# NyanTimer-v7.net
KiCad netlist of a schematic drawn in EAGLE
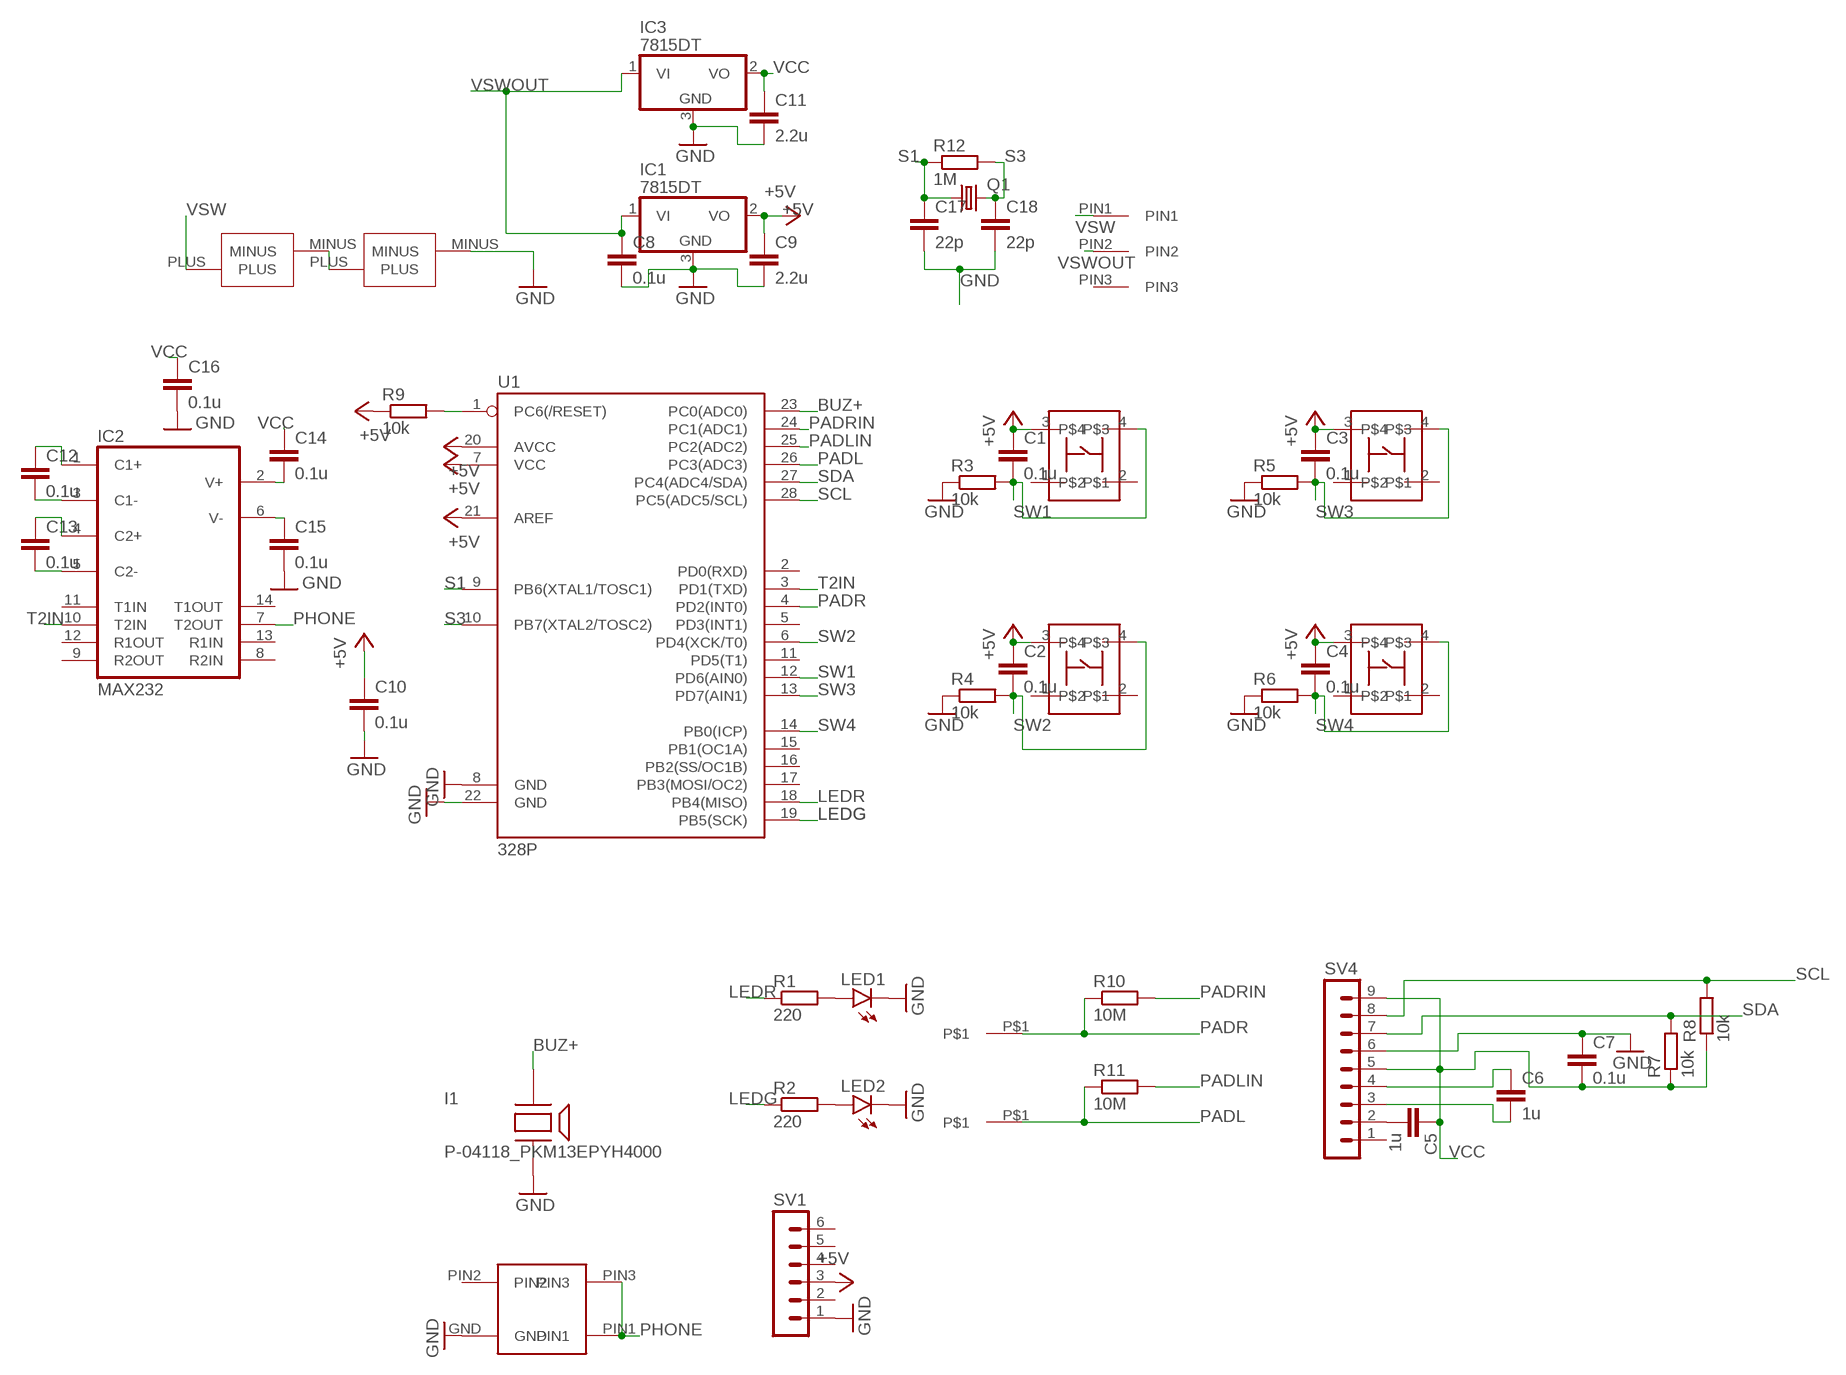
[diagram p0: schematic, sheet 1]

(export (version "E")
  (design (tool "Eeschema 10.0.6"))
  (components
    (comp (ref "BT1")
      (value "AKIZUKI_CR2032")
      (footprint "eagle-import:AKIZUKI_CR2032")
      (libsource (lib "eagle-import") (part "AKIZUKI_CR2032"))
    )
    (comp (ref "BT2")
      (value "AKIZUKI_CR2032")
      (footprint "eagle-import:AKIZUKI_CR2032")
      (libsource (lib "eagle-import") (part "AKIZUKI_CR2032"))
    )
    (comp (ref "C1")
      (value "0.1u")
      (footprint "eagle-import:C025-024X044")
      (libsource (lib "eagle-import") (part "C-EU025-024X044"))
    )
    (comp (ref "C2")
      (value "0.1u")
      (footprint "eagle-import:C025-024X044")
      (libsource (lib "eagle-import") (part "C-EU025-024X044"))
    )
    (comp (ref "C3")
      (value "0.1u")
      (footprint "eagle-import:C025-024X044")
      (libsource (lib "eagle-import") (part "C-EU025-024X044"))
    )
    (comp (ref "C4")
      (value "0.1u")
      (footprint "eagle-import:C025-024X044")
      (libsource (lib "eagle-import") (part "C-EU025-024X044"))
    )
    (comp (ref "C5")
      (value "1u")
      (footprint "eagle-import:C025-024X044")
      (libsource (lib "eagle-import") (part "C-EU025-024X044"))
    )
    (comp (ref "C6")
      (value "1u")
      (footprint "eagle-import:C025-024X044")
      (libsource (lib "eagle-import") (part "C-EU025-024X044"))
    )
    (comp (ref "C7")
      (value "0.1u")
      (footprint "eagle-import:C025-024X044")
      (libsource (lib "eagle-import") (part "C-EU025-024X044"))
    )
    (comp (ref "C8")
      (value "0.1u")
      (footprint "eagle-import:C025-024X044")
      (libsource (lib "eagle-import") (part "C-EU025-024X044"))
    )
    (comp (ref "C9")
      (value "2.2u")
      (footprint "eagle-import:C025-024X044")
      (libsource (lib "eagle-import") (part "C-EU025-024X044"))
    )
    (comp (ref "C10")
      (value "0.1u")
      (footprint "eagle-import:C025-024X044")
      (libsource (lib "eagle-import") (part "C-EU025-024X044"))
    )
    (comp (ref "C11")
      (value "2.2u")
      (footprint "eagle-import:C025-024X044")
      (libsource (lib "eagle-import") (part "C-EU025-024X044"))
    )
    (comp (ref "C12")
      (value "0.1u")
      (footprint "eagle-import:C025-024X044")
      (libsource (lib "eagle-import") (part "C-EU025-024X044"))
    )
    (comp (ref "C13")
      (value "0.1u")
      (footprint "eagle-import:C025-024X044")
      (libsource (lib "eagle-import") (part "C-EU025-024X044"))
    )
    (comp (ref "C14")
      (value "0.1u")
      (footprint "eagle-import:C025-024X044")
      (libsource (lib "eagle-import") (part "C-EU025-024X044"))
    )
    (comp (ref "C15")
      (value "0.1u")
      (footprint "eagle-import:C025-024X044")
      (libsource (lib "eagle-import") (part "C-EU025-024X044"))
    )
    (comp (ref "C16")
      (value "0.1u")
      (footprint "eagle-import:C025-024X044")
      (libsource (lib "eagle-import") (part "C-EU025-024X044"))
    )
    (comp (ref "C17")
      (value "22p")
      (footprint "eagle-import:C025-024X044")
      (libsource (lib "eagle-import") (part "C-EU025-024X044"))
    )
    (comp (ref "C18")
      (value "22p")
      (footprint "eagle-import:C025-024X044")
      (libsource (lib "eagle-import") (part "C-EU025-024X044"))
    )
    (comp (ref "CONNECTOR1")
      (value "TACT_SWITCH")
      (footprint "eagle-import:TACT_SWITCH")
      (libsource (lib "eagle-import") (part "TACT_SWITCH"))
    )
    (comp (ref "CONNECTOR2")
      (value "TACT_SWITCH")
      (footprint "eagle-import:TACT_SWITCH")
      (libsource (lib "eagle-import") (part "TACT_SWITCH"))
    )
    (comp (ref "CONNECTOR3")
      (value "TACT_SWITCH")
      (footprint "eagle-import:TACT_SWITCH")
      (libsource (lib "eagle-import") (part "TACT_SWITCH"))
    )
    (comp (ref "CONNECTOR4")
      (value "TACT_SWITCH")
      (footprint "eagle-import:TACT_SWITCH")
      (libsource (lib "eagle-import") (part "TACT_SWITCH"))
    )
    (comp (ref "I1")
      (value "P-04118_PKM13EPYH4000")
      (footprint "eagle-import:PKM13EPYH4000")
      (libsource (lib "eagle-import") (part "P-04118_PKM13EPYH4000"))
    )
    (comp (ref "IC1")
      (value "7815DT")
      (footprint "eagle-import:TO252")
      (libsource (lib "eagle-import") (part "78DT15"))
    )
    (comp (ref "IC2")
      (value "MAX232")
      (footprint "eagle-import:DIL16")
      (fields (field (name "MF") "MAXIM") (field (name "MPN") "MAX232ACPE+"))
      (libsource (lib "eagle-import") (part "MAX232"))
    )
    (comp (ref "IC3")
      (value "7815DT")
      (footprint "eagle-import:TO252")
      (libsource (lib "eagle-import") (part "78DT15"))
    )
    (comp (ref "LED1")
      (value "LED3MM")
      (footprint "eagle-import:LED3MM")
      (libsource (lib "eagle-import") (part "LED3MM"))
    )
    (comp (ref "LED2")
      (value "LED3MM")
      (footprint "eagle-import:LED3MM")
      (libsource (lib "eagle-import") (part "LED3MM"))
    )
    (comp (ref "PHN1")
      (value "PHONE")
      (footprint "eagle-import:PHONE")
      (libsource (lib "eagle-import") (part "PHONE"))
    )
    (comp (ref "PIN1")
      (value "1PINHEAD")
      (footprint "eagle-import:1PINHEAD")
      (libsource (lib "eagle-import") (part "1PINHEAD"))
    )
    (comp (ref "PIN2")
      (value "1PINHEAD")
      (footprint "eagle-import:1PINHEAD")
      (libsource (lib "eagle-import") (part "1PINHEAD"))
    )
    (comp (ref "Q1")
      (value "CRYSTALHC49S")
      (footprint "eagle-import:HC49_S")
      (libsource (lib "eagle-import") (part "CRYSTALHC49S"))
    )
    (comp (ref "R1")
      (value "220")
      (footprint "eagle-import:0207_10")
      (libsource (lib "eagle-import") (part "R-EU_0207/10"))
    )
    (comp (ref "R2")
      (value "220")
      (footprint "eagle-import:0207_10")
      (libsource (lib "eagle-import") (part "R-EU_0207/10"))
    )
    (comp (ref "R3")
      (value "10k")
      (footprint "eagle-import:0207_10")
      (libsource (lib "eagle-import") (part "R-EU_0207/10"))
    )
    (comp (ref "R4")
      (value "10k")
      (footprint "eagle-import:0207_10")
      (libsource (lib "eagle-import") (part "R-EU_0207/10"))
    )
    (comp (ref "R5")
      (value "10k")
      (footprint "eagle-import:0207_10")
      (libsource (lib "eagle-import") (part "R-EU_0207/10"))
    )
    (comp (ref "R6")
      (value "10k")
      (footprint "eagle-import:0207_10")
      (libsource (lib "eagle-import") (part "R-EU_0207/10"))
    )
    (comp (ref "R7")
      (value "10k")
      (footprint "eagle-import:0207_10")
      (libsource (lib "eagle-import") (part "R-EU_0207/10"))
    )
    (comp (ref "R8")
      (value "10k")
      (footprint "eagle-import:0207_10")
      (libsource (lib "eagle-import") (part "R-EU_0207/10"))
    )
    (comp (ref "R9")
      (value "10k")
      (footprint "eagle-import:0207_10")
      (libsource (lib "eagle-import") (part "R-EU_0207/10"))
    )
    (comp (ref "R10")
      (value "10M")
      (footprint "eagle-import:0207_10")
      (libsource (lib "eagle-import") (part "R-EU_0207/10"))
    )
    (comp (ref "R11")
      (value "10M")
      (footprint "eagle-import:0207_10")
      (libsource (lib "eagle-import") (part "R-EU_0207/10"))
    )
    (comp (ref "R12")
      (value "1M")
      (footprint "eagle-import:0207_10")
      (libsource (lib "eagle-import") (part "R-EU_0207/10"))
    )
    (comp (ref "SV1")
      (value "MA06-1")
      (footprint "eagle-import:MA06-1")
      (libsource (lib "eagle-import") (part "MA06-1"))
    )
    (comp (ref "SV4")
      (value "MA09-1")
      (footprint "eagle-import:MA09-1")
      (libsource (lib "eagle-import") (part "MA09-1"))
    )
    (comp (ref "SW1")
      (value "AKIZUKI_SWITCH")
      (footprint "eagle-import:AKIZUKI_SWITCH")
      (libsource (lib "eagle-import") (part "AKIZUKI_SWITCH"))
    )
    (comp (ref "U1")
      (value "328P")
      (footprint "eagle-import:DIP28")
      (libsource (lib "eagle-import") (part "ATMEGA328P_PDIP"))
    )
  )
  (nets
    (net (code "1") (name "+5V") (class "Default")
      (node (ref "C1") (pin "1") (pinfunction "1_1") (pintype "passive"))
      (node (ref "C10") (pin "1") (pinfunction "1_1") (pintype "passive"))
      (node (ref "C2") (pin "1") (pinfunction "1_1") (pintype "passive"))
      (node (ref "C3") (pin "1") (pinfunction "1_1") (pintype "passive"))
      (node (ref "C4") (pin "1") (pinfunction "1_1") (pintype "passive"))
      (node (ref "C9") (pin "1") (pinfunction "1_1") (pintype "passive"))
      (node (ref "CONNECTOR1") (pin "3") (pinfunction "P$3_3") (pintype "bidirectional"))
      (node (ref "CONNECTOR2") (pin "3") (pinfunction "P$3_3") (pintype "bidirectional"))
      (node (ref "CONNECTOR3") (pin "3") (pinfunction "P$3_3") (pintype "bidirectional"))
      (node (ref "CONNECTOR4") (pin "3") (pinfunction "P$3_3") (pintype "bidirectional"))
      (node (ref "IC1") (pin "2") (pinfunction "VO_2") (pintype "passive"))
      (node (ref "R9") (pin "1") (pinfunction "1_1") (pintype "passive"))
      (node (ref "SV1") (pin "3") (pinfunction "3_3") (pintype "passive"))
      (node (ref "U1") (pin "20") (pinfunction "AVCC_20") (pintype "bidirectional"))
      (node (ref "U1") (pin "21") (pinfunction "AREF_21") (pintype "bidirectional"))
      (node (ref "U1") (pin "7") (pinfunction "VCC_7") (pintype "bidirectional"))
    )
    (net (code "2") (name "/BUZ+") (class "Default")
      (node (ref "I1") (pin "1") (pinfunction "1_1") (pintype "bidirectional"))
      (node (ref "U1") (pin "23") (pinfunction "PC0(ADC0)_23") (pintype "bidirectional"))
    )
    (net (code "3") (name "/LEDG") (class "Default")
      (node (ref "R2") (pin "1") (pinfunction "1_1") (pintype "passive"))
      (node (ref "U1") (pin "19") (pinfunction "PB5(SCK)_19") (pintype "bidirectional"))
    )
    (net (code "4") (name "/LEDR") (class "Default")
      (node (ref "R1") (pin "1") (pinfunction "1_1") (pintype "passive"))
      (node (ref "U1") (pin "18") (pinfunction "PB4(MISO)_18") (pintype "bidirectional"))
    )
    (net (code "5") (name "/PADL") (class "Default")
      (node (ref "PIN1") (pin "P$1") (pinfunction "P$1_P$1") (pintype "bidirectional"))
      (node (ref "R11") (pin "1") (pinfunction "1_1") (pintype "passive"))
      (node (ref "U1") (pin "26") (pinfunction "PC3(ADC3)_26") (pintype "bidirectional"))
    )
    (net (code "6") (name "/PADLIN") (class "Default")
      (node (ref "R11") (pin "2") (pinfunction "2_2") (pintype "passive"))
      (node (ref "U1") (pin "25") (pinfunction "PC2(ADC2)_25") (pintype "bidirectional"))
    )
    (net (code "7") (name "/PADR") (class "Default")
      (node (ref "PIN2") (pin "P$1") (pinfunction "P$1_P$1") (pintype "bidirectional"))
      (node (ref "R10") (pin "1") (pinfunction "1_1") (pintype "passive"))
      (node (ref "U1") (pin "4") (pinfunction "PD2(INT0)_4") (pintype "bidirectional"))
    )
    (net (code "8") (name "/PADRIN") (class "Default")
      (node (ref "R10") (pin "2") (pinfunction "2_2") (pintype "passive"))
      (node (ref "U1") (pin "24") (pinfunction "PC1(ADC1)_24") (pintype "bidirectional"))
    )
    (net (code "9") (name "/PHONE") (class "Default")
      (node (ref "IC2") (pin "7") (pinfunction "T2OUT_7") (pintype "output"))
      (node (ref "PHN1") (pin "PIN1") (pinfunction "PIN1_PIN1") (pintype "bidirectional"))
      (node (ref "PHN1") (pin "PIN3") (pinfunction "PIN3_PIN3") (pintype "bidirectional"))
    )
    (net (code "10") (name "/S1") (class "Default")
      (node (ref "C17") (pin "1") (pinfunction "1_1") (pintype "passive"))
      (node (ref "Q1") (pin "1") (pinfunction "1_1") (pintype "passive"))
      (node (ref "R12") (pin "1") (pinfunction "1_1") (pintype "passive"))
      (node (ref "U1") (pin "9") (pinfunction "PB6(XTAL1/TOSC1)_9") (pintype "bidirectional"))
    )
    (net (code "11") (name "/S3") (class "Default")
      (node (ref "C18") (pin "1") (pinfunction "1_1") (pintype "passive"))
      (node (ref "Q1") (pin "2") (pinfunction "2_2") (pintype "passive"))
      (node (ref "R12") (pin "2") (pinfunction "2_2") (pintype "passive"))
      (node (ref "U1") (pin "10") (pinfunction "PB7(XTAL2/TOSC2)_10") (pintype "bidirectional"))
    )
    (net (code "12") (name "/SCL") (class "Default")
      (node (ref "R8") (pin "2") (pinfunction "2_2") (pintype "passive"))
      (node (ref "SV4") (pin "8") (pinfunction "8_8") (pintype "passive"))
      (node (ref "U1") (pin "28") (pinfunction "PC5(ADC5/SCL)_28") (pintype "bidirectional"))
    )
    (net (code "13") (name "/SDA") (class "Default")
      (node (ref "R7") (pin "2") (pinfunction "2_2") (pintype "passive"))
      (node (ref "SV4") (pin "7") (pinfunction "7_7") (pintype "passive"))
      (node (ref "U1") (pin "27") (pinfunction "PC4(ADC4/SDA)_27") (pintype "bidirectional"))
    )
    (net (code "14") (name "/SW1") (class "Default")
      (node (ref "C1") (pin "2") (pinfunction "2_2") (pintype "passive"))
      (node (ref "CONNECTOR1") (pin "4") (pinfunction "P$4_4") (pintype "bidirectional"))
      (node (ref "R3") (pin "2") (pinfunction "2_2") (pintype "passive"))
      (node (ref "U1") (pin "12") (pinfunction "PD6(AIN0)_12") (pintype "bidirectional"))
    )
    (net (code "15") (name "/SW2") (class "Default")
      (node (ref "C2") (pin "2") (pinfunction "2_2") (pintype "passive"))
      (node (ref "CONNECTOR2") (pin "4") (pinfunction "P$4_4") (pintype "bidirectional"))
      (node (ref "R4") (pin "2") (pinfunction "2_2") (pintype "passive"))
      (node (ref "U1") (pin "6") (pinfunction "PD4(XCK/T0)_6") (pintype "bidirectional"))
    )
    (net (code "16") (name "/SW3") (class "Default")
      (node (ref "C3") (pin "2") (pinfunction "2_2") (pintype "passive"))
      (node (ref "CONNECTOR3") (pin "4") (pinfunction "P$4_4") (pintype "bidirectional"))
      (node (ref "R5") (pin "2") (pinfunction "2_2") (pintype "passive"))
      (node (ref "U1") (pin "13") (pinfunction "PD7(AIN1)_13") (pintype "bidirectional"))
    )
    (net (code "17") (name "/SW4") (class "Default")
      (node (ref "C4") (pin "2") (pinfunction "2_2") (pintype "passive"))
      (node (ref "CONNECTOR4") (pin "4") (pinfunction "P$4_4") (pintype "bidirectional"))
      (node (ref "R6") (pin "2") (pinfunction "2_2") (pintype "passive"))
      (node (ref "U1") (pin "14") (pinfunction "PB0(ICP)_14") (pintype "bidirectional"))
    )
    (net (code "18") (name "/T2IN") (class "Default")
      (node (ref "IC2") (pin "10") (pinfunction "T2IN_10") (pintype "input"))
      (node (ref "U1") (pin "3") (pinfunction "PD1(TXD)_3") (pintype "bidirectional"))
    )
    (net (code "19") (name "/VCC") (class "Default")
      (node (ref "C11") (pin "1") (pinfunction "1_1") (pintype "passive"))
      (node (ref "C14") (pin "1") (pinfunction "1_1") (pintype "passive"))
      (node (ref "C16") (pin "1") (pinfunction "1_1") (pintype "passive"))
      (node (ref "C5") (pin "1") (pinfunction "1_1") (pintype "passive"))
      (node (ref "C7") (pin "2") (pinfunction "2_2") (pintype "passive"))
      (node (ref "IC3") (pin "2") (pinfunction "VO_2") (pintype "passive"))
      (node (ref "R7") (pin "1") (pinfunction "1_1") (pintype "passive"))
      (node (ref "R8") (pin "1") (pinfunction "1_1") (pintype "passive"))
      (node (ref "SV4") (pin "5") (pinfunction "5_5") (pintype "passive"))
      (node (ref "SV4") (pin "9") (pinfunction "9_9") (pintype "passive"))
    )
    (net (code "20") (name "/VSW") (class "Default")
      (node (ref "BT1") (pin "PLUS") (pinfunction "PLUS_PLUS") (pintype "bidirectional"))
      (node (ref "SW1") (pin "PIN1") (pinfunction "PIN1_PIN1") (pintype "bidirectional"))
    )
    (net (code "21") (name "/VSWOUT") (class "Default")
      (node (ref "C8") (pin "1") (pinfunction "1_1") (pintype "passive"))
      (node (ref "IC1") (pin "1") (pinfunction "VI_1") (pintype "input"))
      (node (ref "IC3") (pin "1") (pinfunction "VI_1") (pintype "input"))
      (node (ref "SW1") (pin "PIN2") (pinfunction "PIN2_PIN2") (pintype "bidirectional"))
    )
    (net (code "22") (name "GND") (class "Default")
      (node (ref "BT2") (pin "MINUS") (pinfunction "MINUS_MINUS") (pintype "bidirectional"))
      (node (ref "C10") (pin "2") (pinfunction "2_2") (pintype "passive"))
      (node (ref "C11") (pin "2") (pinfunction "2_2") (pintype "passive"))
      (node (ref "C15") (pin "2") (pinfunction "2_2") (pintype "passive"))
      (node (ref "C16") (pin "2") (pinfunction "2_2") (pintype "passive"))
      (node (ref "C17") (pin "2") (pinfunction "2_2") (pintype "passive"))
      (node (ref "C18") (pin "2") (pinfunction "2_2") (pintype "passive"))
      (node (ref "C7") (pin "1") (pinfunction "1_1") (pintype "passive"))
      (node (ref "C8") (pin "2") (pinfunction "2_2") (pintype "passive"))
      (node (ref "C9") (pin "2") (pinfunction "2_2") (pintype "passive"))
      (node (ref "I1") (pin "2") (pinfunction "2_2") (pintype "bidirectional"))
      (node (ref "IC1") (pin "3") (pinfunction "GND_3") (pintype "passive"))
      (node (ref "IC3") (pin "3") (pinfunction "GND_3") (pintype "passive"))
      (node (ref "LED1") (pin "K") (pinfunction "C_K") (pintype "passive"))
      (node (ref "LED2") (pin "K") (pinfunction "C_K") (pintype "passive"))
      (node (ref "PHN1") (pin "GND") (pinfunction "GND_GND") (pintype "bidirectional"))
      (node (ref "R3") (pin "1") (pinfunction "1_1") (pintype "passive"))
      (node (ref "R4") (pin "1") (pinfunction "1_1") (pintype "passive"))
      (node (ref "R5") (pin "1") (pinfunction "1_1") (pintype "passive"))
      (node (ref "R6") (pin "1") (pinfunction "1_1") (pintype "passive"))
      (node (ref "SV1") (pin "1") (pinfunction "1_1") (pintype "passive"))
      (node (ref "SV4") (pin "6") (pinfunction "6_6") (pintype "passive"))
      (node (ref "U1") (pin "22") (pinfunction "GND_22") (pintype "bidirectional"))
      (node (ref "U1") (pin "8") (pinfunction "GND_8") (pintype "bidirectional"))
    )
    (net (code "23") (name "Net-(BT1-PadMINUS)") (class "Default")
      (node (ref "BT1") (pin "MINUS") (pinfunction "MINUS_MINUS") (pintype "bidirectional"))
      (node (ref "BT2") (pin "PLUS") (pinfunction "PLUS_PLUS") (pintype "bidirectional"))
    )
    (net (code "24") (name "Net-(C5-Pad2)") (class "Default")
      (node (ref "C5") (pin "2") (pinfunction "2_2") (pintype "passive"))
      (node (ref "SV4") (pin "2") (pinfunction "2_2") (pintype "passive"))
    )
    (net (code "25") (name "Net-(C6-Pad1)") (class "Default")
      (node (ref "C6") (pin "1") (pinfunction "1_1") (pintype "passive"))
      (node (ref "SV4") (pin "4") (pinfunction "4_4") (pintype "passive"))
    )
    (net (code "26") (name "Net-(C6-Pad2)") (class "Default")
      (node (ref "C6") (pin "2") (pinfunction "2_2") (pintype "passive"))
      (node (ref "SV4") (pin "3") (pinfunction "3_3") (pintype "passive"))
    )
    (net (code "27") (name "Net-(IC2A-C1+)") (class "Default")
      (node (ref "C12") (pin "1") (pinfunction "1_1") (pintype "passive"))
      (node (ref "IC2") (pin "1") (pinfunction "C1+_1") (pintype "bidirectional"))
    )
    (net (code "28") (name "Net-(IC2A-C1-)") (class "Default")
      (node (ref "C12") (pin "2") (pinfunction "2_2") (pintype "passive"))
      (node (ref "IC2") (pin "3") (pinfunction "C1-_3") (pintype "bidirectional"))
    )
    (net (code "29") (name "Net-(IC2A-C2+)") (class "Default")
      (node (ref "C13") (pin "1") (pinfunction "1_1") (pintype "passive"))
      (node (ref "IC2") (pin "4") (pinfunction "C2+_4") (pintype "bidirectional"))
    )
    (net (code "30") (name "Net-(IC2A-C2-)") (class "Default")
      (node (ref "C13") (pin "2") (pinfunction "2_2") (pintype "passive"))
      (node (ref "IC2") (pin "5") (pinfunction "C2-_5") (pintype "bidirectional"))
    )
    (net (code "31") (name "Net-(IC2A-V+)") (class "Default")
      (node (ref "C14") (pin "2") (pinfunction "2_2") (pintype "passive"))
      (node (ref "IC2") (pin "2") (pinfunction "V+_2") (pintype "bidirectional"))
    )
    (net (code "32") (name "Net-(IC2A-V-)") (class "Default")
      (node (ref "C15") (pin "1") (pinfunction "1_1") (pintype "passive"))
      (node (ref "IC2") (pin "6") (pinfunction "V-_6") (pintype "bidirectional"))
    )
    (net (code "33") (name "Net-(LED1-PadA)") (class "Default")
      (node (ref "LED1") (pin "A") (pinfunction "A_A") (pintype "passive"))
      (node (ref "R1") (pin "2") (pinfunction "2_2") (pintype "passive"))
    )
    (net (code "34") (name "Net-(LED2-PadA)") (class "Default")
      (node (ref "LED2") (pin "A") (pinfunction "A_A") (pintype "passive"))
      (node (ref "R2") (pin "2") (pinfunction "2_2") (pintype "passive"))
    )
    (net (code "35") (name "Net-(U1-PC6({slash}RESET))") (class "Default")
      (node (ref "R9") (pin "2") (pinfunction "2_2") (pintype "passive"))
      (node (ref "U1") (pin "1") (pinfunction "PC6(/RESET)_1") (pintype "bidirectional"))
    )
    (net (code "36") (name "unconnected-(CONNECTOR1-P$1-Pad1)") (class "Default")
      (node (ref "CONNECTOR1") (pin "1") (pinfunction "P$1_1") (pintype "bidirectional"))
    )
    (net (code "37") (name "unconnected-(CONNECTOR1-P$2-Pad2)") (class "Default")
      (node (ref "CONNECTOR1") (pin "2") (pinfunction "P$2_2") (pintype "bidirectional"))
    )
    (net (code "38") (name "unconnected-(CONNECTOR2-P$1-Pad1)") (class "Default")
      (node (ref "CONNECTOR2") (pin "1") (pinfunction "P$1_1") (pintype "bidirectional"))
    )
    (net (code "39") (name "unconnected-(CONNECTOR2-P$2-Pad2)") (class "Default")
      (node (ref "CONNECTOR2") (pin "2") (pinfunction "P$2_2") (pintype "bidirectional"))
    )
    (net (code "40") (name "unconnected-(CONNECTOR3-P$1-Pad1)") (class "Default")
      (node (ref "CONNECTOR3") (pin "1") (pinfunction "P$1_1") (pintype "bidirectional"))
    )
    (net (code "41") (name "unconnected-(CONNECTOR3-P$2-Pad2)") (class "Default")
      (node (ref "CONNECTOR3") (pin "2") (pinfunction "P$2_2") (pintype "bidirectional"))
    )
    (net (code "42") (name "unconnected-(CONNECTOR4-P$1-Pad1)") (class "Default")
      (node (ref "CONNECTOR4") (pin "1") (pinfunction "P$1_1") (pintype "bidirectional"))
    )
    (net (code "43") (name "unconnected-(CONNECTOR4-P$2-Pad2)") (class "Default")
      (node (ref "CONNECTOR4") (pin "2") (pinfunction "P$2_2") (pintype "bidirectional"))
    )
    (net (code "44") (name "unconnected-(IC2A-R1IN-Pad13)") (class "Default")
      (node (ref "IC2") (pin "13") (pinfunction "R1IN_13") (pintype "input"))
    )
    (net (code "45") (name "unconnected-(IC2A-R1OUT-Pad12)") (class "Default")
      (node (ref "IC2") (pin "12") (pinfunction "R1OUT_12") (pintype "output"))
    )
    (net (code "46") (name "unconnected-(IC2A-R2IN-Pad8)") (class "Default")
      (node (ref "IC2") (pin "8") (pinfunction "R2IN_8") (pintype "input"))
    )
    (net (code "47") (name "unconnected-(IC2A-R2OUT-Pad9)") (class "Default")
      (node (ref "IC2") (pin "9") (pinfunction "R2OUT_9") (pintype "output"))
    )
    (net (code "48") (name "unconnected-(IC2A-T1IN-Pad11)") (class "Default")
      (node (ref "IC2") (pin "11") (pinfunction "T1IN_11") (pintype "input"))
    )
    (net (code "49") (name "unconnected-(IC2A-T1OUT-Pad14)") (class "Default")
      (node (ref "IC2") (pin "14") (pinfunction "T1OUT_14") (pintype "output"))
    )
    (net (code "50") (name "unconnected-(PHN1-PadPIN2)") (class "Default")
      (node (ref "PHN1") (pin "PIN2") (pinfunction "PIN2_PIN2") (pintype "bidirectional"))
    )
    (net (code "51") (name "unconnected-(SV1-Pad2)") (class "Default")
      (node (ref "SV1") (pin "2") (pinfunction "2_2") (pintype "passive"))
    )
    (net (code "52") (name "unconnected-(SV1-Pad4)") (class "Default")
      (node (ref "SV1") (pin "4") (pinfunction "4_4") (pintype "passive"))
    )
    (net (code "53") (name "unconnected-(SV1-Pad5)") (class "Default")
      (node (ref "SV1") (pin "5") (pinfunction "5_5") (pintype "passive"))
    )
    (net (code "54") (name "unconnected-(SV1-Pad6)") (class "Default")
      (node (ref "SV1") (pin "6") (pinfunction "6_6") (pintype "passive"))
    )
    (net (code "55") (name "unconnected-(SV4-Pad1)") (class "Default")
      (node (ref "SV4") (pin "1") (pinfunction "1_1") (pintype "passive"))
    )
    (net (code "56") (name "unconnected-(SW1-PadPIN3)") (class "Default")
      (node (ref "SW1") (pin "PIN3") (pinfunction "PIN3_PIN3") (pintype "bidirectional"))
    )
    (net (code "57") (name "unconnected-(U1-PB1(OC1A)-Pad15)") (class "Default")
      (node (ref "U1") (pin "15") (pinfunction "PB1(OC1A)_15") (pintype "bidirectional"))
    )
    (net (code "58") (name "unconnected-(U1-PB2(SS{slash}OC1B)-Pad16)") (class "Default")
      (node (ref "U1") (pin "16") (pinfunction "PB2(SS/OC1B)_16") (pintype "bidirectional"))
    )
    (net (code "59") (name "unconnected-(U1-PB3(MOSI{slash}OC2)-Pad17)") (class "Default")
      (node (ref "U1") (pin "17") (pinfunction "PB3(MOSI/OC2)_17") (pintype "bidirectional"))
    )
    (net (code "60") (name "unconnected-(U1-PD0(RXD)-Pad2)") (class "Default")
      (node (ref "U1") (pin "2") (pinfunction "PD0(RXD)_2") (pintype "bidirectional"))
    )
    (net (code "61") (name "unconnected-(U1-PD3(INT1)-Pad5)") (class "Default")
      (node (ref "U1") (pin "5") (pinfunction "PD3(INT1)_5") (pintype "bidirectional"))
    )
    (net (code "62") (name "unconnected-(U1-PD5(T1)-Pad11)") (class "Default")
      (node (ref "U1") (pin "11") (pinfunction "PD5(T1)_11") (pintype "bidirectional"))
    )
  )
)
